# untitled.net
KiCad netlist of a schematic drawn in EAGLE
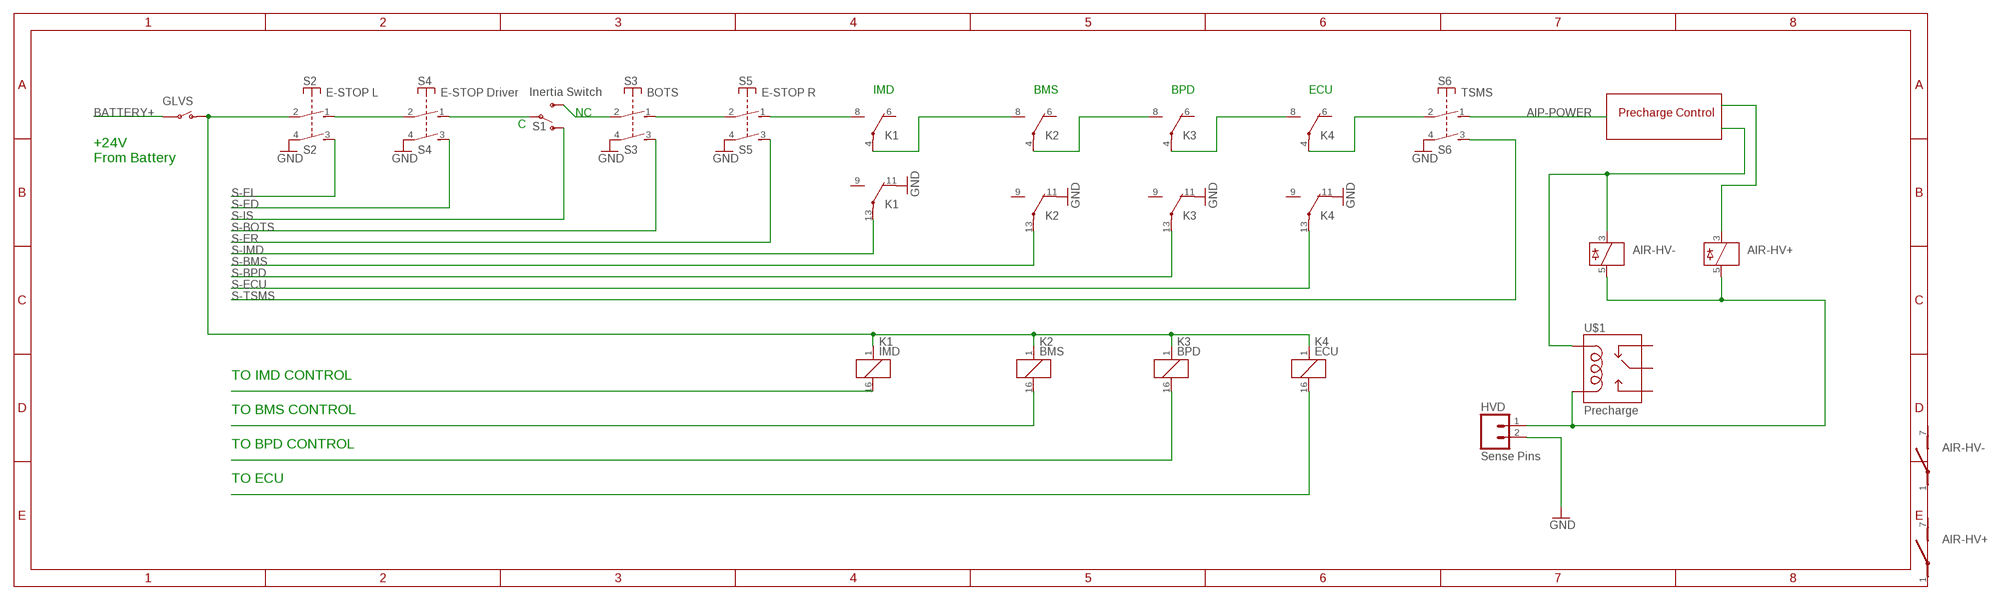
[diagram p0: schematic, sheet 1]
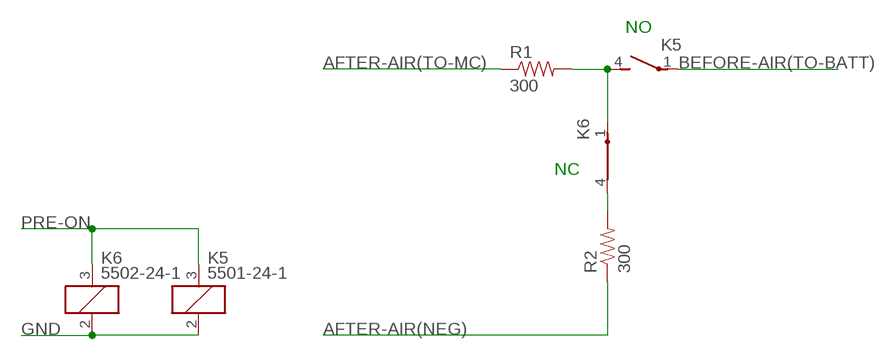
[diagram p1: schematic, sheet 2]

(export (version "E")
  (design (tool "Eeschema 10.0.6"))
  (components
    (comp (ref "K5")
      (value "5501-24-1")
      (footprint "eagle-import:5500")
      (libsource (lib "eagle-import") (part "5501-24-1"))
    )
    (comp (ref "K6")
      (value "5502-24-1")
      (footprint "eagle-import:5500")
      (libsource (lib "eagle-import") (part "5502-24-1"))
    )
    (comp (ref "R1")
      (value "300")
      (footprint "eagle-import:0603-RES")
      (libsource (lib "eagle-import") (part "1MOHM1/10W1%(0603)"))
    )
    (comp (ref "R2")
      (value "300")
      (footprint "eagle-import:0603-RES")
      (libsource (lib "eagle-import") (part "1MOHM1/10W1%(0603)"))
    )
    (comp (ref "AIR-HV+")
      (value "35701331")
      (footprint "eagle-import:REED")
      (libsource (lib "eagle-import") (part "35701331"))
    )
    (comp (ref "AIR-HV-")
      (value "35701331")
      (footprint "eagle-import:REED")
      (libsource (lib "eagle-import") (part "35701331"))
    )
    (comp (ref "GLVS")
      (value "SWITCH-SPST-2TV")
      (footprint "eagle-import:SWITCH-SPST-VERTICAL")
      (libsource (lib "eagle-import") (part "SWITCH-SPST-2TV"))
    )
    (comp (ref "HVD")
      (value "Sense Pins")
      (footprint "eagle-import:JST-2-SMD")
      (libsource (lib "eagle-import") (part "M02-JST-2MM-SMT"))
    )
    (comp (ref "K1")
      (value "IMD")
      (footprint "eagle-import:BT-XX-S")
      (libsource (lib "eagle-import") (part "BT--S6"))
    )
    (comp (ref "K2")
      (value "BMS")
      (footprint "eagle-import:BT-XX-S")
      (libsource (lib "eagle-import") (part "BT--S6"))
    )
    (comp (ref "K3")
      (value "BPD")
      (footprint "eagle-import:BT-XX-S")
      (libsource (lib "eagle-import") (part "BT--S6"))
    )
    (comp (ref "K4")
      (value "ECU")
      (footprint "eagle-import:BT-XX-S")
      (libsource (lib "eagle-import") (part "BT--S6"))
    )
    (comp (ref "S1")
      (value "Inertia Switch")
      (footprint "eagle-import:SWITCHE-DPDT")
      (libsource (lib "eagle-import") (part "SWITCH-SPDTPTH2"))
    )
    (comp (ref "S2")
      (value "E-STOP L")
      (footprint "eagle-import:PVA1F")
      (libsource (lib "eagle-import") (part "PVA1"))
    )
    (comp (ref "S3")
      (value "BOTS")
      (footprint "eagle-import:PVA1F")
      (libsource (lib "eagle-import") (part "PVA1"))
    )
    (comp (ref "S4")
      (value "E-STOP Driver")
      (footprint "eagle-import:PVA1F")
      (libsource (lib "eagle-import") (part "PVA1"))
    )
    (comp (ref "S5")
      (value "E-STOP R")
      (footprint "eagle-import:PVA1F")
      (libsource (lib "eagle-import") (part "PVA1"))
    )
    (comp (ref "S6")
      (value "TSMS")
      (footprint "eagle-import:PVA1F")
      (libsource (lib "eagle-import") (part "PVA1"))
    )
    (comp (ref "U$1")
      (value "Precharge")
      (footprint "eagle-import:RELAY-G5Q")
      (libsource (lib "eagle-import") (part "RELAYPTH"))
    )
  )
  (nets
    (net (code "1") (name "AFTER-AIR(NEG)") (class "Default")
      (node (ref "R2") (pin "1") (pinfunction "1_1") (pintype "passive"))
    )
    (net (code "2") (name "AFTER-AIR(TO-MC)") (class "Default")
      (node (ref "R1") (pin "1") (pinfunction "1_1") (pintype "passive"))
    )
    (net (code "3") (name "AIP-POWER") (class "Default")
      (node (ref "S6") (pin "1") (pinfunction "S_1") (pintype "passive"))
    )
    (net (code "4") (name "BATTERY+") (class "Default")
      (node (ref "GLVS") (pin "2") (pinfunction "P_2") (pintype "passive"))
    )
    (net (code "5") (name "BEFORE-AIR(TO-BATT)") (class "Default")
      (node (ref "K5") (pin "1") (pinfunction "P_1") (pintype "passive"))
    )
    (net (code "6") (name "GND") (class "Default")
      (node (ref "HVD") (pin "2") (pinfunction "1_2") (pintype "passive"))
      (node (ref "K1") (pin "11") (pinfunction "O_11") (pintype "passive"))
      (node (ref "K2") (pin "11") (pinfunction "O_11") (pintype "passive"))
      (node (ref "K3") (pin "11") (pinfunction "O_11") (pintype "passive"))
      (node (ref "K4") (pin "11") (pinfunction "O_11") (pintype "passive"))
      (node (ref "K5") (pin "2") (pinfunction "-_2") (pintype "passive"))
      (node (ref "K6") (pin "2") (pinfunction "-_2") (pintype "passive"))
      (node (ref "S2") (pin "4") (pinfunction "P_4") (pintype "passive"))
      (node (ref "S3") (pin "4") (pinfunction "P_4") (pintype "passive"))
      (node (ref "S4") (pin "4") (pinfunction "P_4") (pintype "passive"))
      (node (ref "S5") (pin "4") (pinfunction "P_4") (pintype "passive"))
      (node (ref "S6") (pin "4") (pinfunction "P_4") (pintype "passive"))
    )
    (net (code "7") (name "Net-(GLVS-O)") (class "Default")
      (node (ref "GLVS") (pin "1") (pinfunction "O_1") (pintype "passive"))
      (node (ref "K1") (pin "1") (pinfunction "1_1") (pintype "passive"))
      (node (ref "K2") (pin "1") (pinfunction "1_1") (pintype "passive"))
      (node (ref "K3") (pin "1") (pinfunction "1_1") (pintype "passive"))
      (node (ref "K4") (pin "1") (pinfunction "1_1") (pintype "passive"))
      (node (ref "S2") (pin "2") (pinfunction "P_2") (pintype "passive"))
    )
    (net (code "8") (name "Net-(HVD-2)") (class "Default")
      (node (ref "AIR-HV+") (pin "5") (pinfunction "5_5") (pintype "passive"))
      (node (ref "AIR-HV-") (pin "5") (pinfunction "5_5") (pintype "passive"))
      (node (ref "HVD") (pin "1") (pinfunction "2_1") (pintype "passive"))
      (node (ref "U$1") (pin "1") (pinfunction "COIL2_1") (pintype "bidirectional"))
    )
    (net (code "9") (name "Net-(K1A-P)") (class "Default")
      (node (ref "K1") (pin "4") (pinfunction "P_4") (pintype "passive"))
      (node (ref "K2") (pin "8") (pinfunction "S_8") (pintype "passive"))
    )
    (net (code "10") (name "Net-(K1A-S)") (class "Default")
      (node (ref "K1") (pin "8") (pinfunction "S_8") (pintype "passive"))
      (node (ref "S5") (pin "1") (pinfunction "S_1") (pintype "passive"))
    )
    (net (code "11") (name "Net-(K2A-P)") (class "Default")
      (node (ref "K2") (pin "4") (pinfunction "P_4") (pintype "passive"))
      (node (ref "K3") (pin "8") (pinfunction "S_8") (pintype "passive"))
    )
    (net (code "12") (name "Net-(K3A-P)") (class "Default")
      (node (ref "K3") (pin "4") (pinfunction "P_4") (pintype "passive"))
      (node (ref "K4") (pin "8") (pinfunction "S_8") (pintype "passive"))
    )
    (net (code "13") (name "Net-(K4A-P)") (class "Default")
      (node (ref "K4") (pin "4") (pinfunction "P_4") (pintype "passive"))
      (node (ref "S6") (pin "2") (pinfunction "P_2") (pintype "passive"))
    )
    (net (code "14") (name "Net-(K5B-S)") (class "Default")
      (node (ref "K5") (pin "4") (pinfunction "S_4") (pintype "passive"))
      (node (ref "K6") (pin "1") (pinfunction "P_1") (pintype "passive"))
      (node (ref "R1") (pin "2") (pinfunction "2_2") (pintype "passive"))
    )
    (net (code "15") (name "Net-(K6B-S)") (class "Default")
      (node (ref "K6") (pin "4") (pinfunction "S_4") (pintype "passive"))
      (node (ref "R2") (pin "2") (pinfunction "2_2") (pintype "passive"))
    )
    (net (code "16") (name "Net-(S1-P)") (class "Default")
      (node (ref "S1") (pin "2") (pinfunction "P_2") (pintype "passive"))
      (node (ref "S4") (pin "1") (pinfunction "S_1") (pintype "passive"))
    )
    (net (code "17") (name "Net-(S1-S)") (class "Default")
      (node (ref "S1") (pin "3") (pinfunction "S_3") (pintype "passive"))
      (node (ref "S3") (pin "2") (pinfunction "P_2") (pintype "passive"))
    )
    (net (code "18") (name "Net-(S2A-S)") (class "Default")
      (node (ref "S2") (pin "1") (pinfunction "S_1") (pintype "passive"))
      (node (ref "S4") (pin "2") (pinfunction "P_2") (pintype "passive"))
    )
    (net (code "19") (name "Net-(S3A-S)") (class "Default")
      (node (ref "S3") (pin "1") (pinfunction "S_1") (pintype "passive"))
      (node (ref "S5") (pin "2") (pinfunction "P_2") (pintype "passive"))
    )
    (net (code "20") (name "Net-(U$1-COIL1)") (class "Default")
      (node (ref "AIR-HV-") (pin "3") (pinfunction "3_3") (pintype "passive"))
      (node (ref "U$1") (pin "5") (pinfunction "COIL1_5") (pintype "bidirectional"))
    )
    (net (code "21") (name "PRE-ON") (class "Default")
      (node (ref "K5") (pin "3") (pinfunction "+_3") (pintype "passive"))
      (node (ref "K6") (pin "3") (pinfunction "+_3") (pintype "passive"))
    )
    (net (code "22") (name "S-BMS") (class "Default")
      (node (ref "K2") (pin "13") (pinfunction "P_13") (pintype "passive"))
    )
    (net (code "23") (name "S-BOTS") (class "Default")
      (node (ref "S3") (pin "3") (pinfunction "S_3") (pintype "passive"))
    )
    (net (code "24") (name "S-BPD") (class "Default")
      (node (ref "K3") (pin "13") (pinfunction "P_13") (pintype "passive"))
    )
    (net (code "25") (name "S-ECU") (class "Default")
      (node (ref "K4") (pin "13") (pinfunction "P_13") (pintype "passive"))
    )
    (net (code "26") (name "S-ED") (class "Default")
      (node (ref "S4") (pin "3") (pinfunction "S_3") (pintype "passive"))
    )
    (net (code "27") (name "S-EL") (class "Default")
      (node (ref "S2") (pin "3") (pinfunction "S_3") (pintype "passive"))
    )
    (net (code "28") (name "S-ER") (class "Default")
      (node (ref "S5") (pin "3") (pinfunction "S_3") (pintype "passive"))
    )
    (net (code "29") (name "S-IMD") (class "Default")
      (node (ref "K1") (pin "13") (pinfunction "P_13") (pintype "passive"))
    )
    (net (code "30") (name "S-IS") (class "Default")
      (node (ref "S1") (pin "1") (pinfunction "O_1") (pintype "passive"))
    )
    (net (code "31") (name "S-TSMS") (class "Default")
      (node (ref "S6") (pin "3") (pinfunction "S_3") (pintype "passive"))
    )
    (net (code "32") (name "unconnected-(AIR-HV+-Pad3)") (class "Default")
      (node (ref "AIR-HV+") (pin "3") (pinfunction "3_3") (pintype "passive"))
    )
    (net (code "33") (name "unconnected-(AIR-HV+B-P-Pad1)") (class "Default")
      (node (ref "AIR-HV+") (pin "1") (pinfunction "P_1") (pintype "passive"))
    )
    (net (code "34") (name "unconnected-(AIR-HV+B-S-Pad7)") (class "Default")
      (node (ref "AIR-HV+") (pin "7") (pinfunction "S_7") (pintype "passive"))
    )
    (net (code "35") (name "unconnected-(AIR-HV-B-P-Pad1)") (class "Default")
      (node (ref "AIR-HV-") (pin "1") (pinfunction "P_1") (pintype "passive"))
    )
    (net (code "36") (name "unconnected-(AIR-HV-B-S-Pad7)") (class "Default")
      (node (ref "AIR-HV-") (pin "7") (pinfunction "S_7") (pintype "passive"))
    )
    (net (code "37") (name "unconnected-(K1A-O-Pad6)") (class "Default")
      (node (ref "K1") (pin "6") (pinfunction "O_6") (pintype "passive"))
    )
    (net (code "38") (name "unconnected-(K1B-S-Pad9)") (class "Default")
      (node (ref "K1") (pin "9") (pinfunction "S_9") (pintype "passive"))
    )
    (net (code "39") (name "unconnected-(K1C-2-Pad16)") (class "Default")
      (node (ref "K1") (pin "16") (pinfunction "2_16") (pintype "passive"))
    )
    (net (code "40") (name "unconnected-(K2A-O-Pad6)") (class "Default")
      (node (ref "K2") (pin "6") (pinfunction "O_6") (pintype "passive"))
    )
    (net (code "41") (name "unconnected-(K2B-S-Pad9)") (class "Default")
      (node (ref "K2") (pin "9") (pinfunction "S_9") (pintype "passive"))
    )
    (net (code "42") (name "unconnected-(K2C-2-Pad16)") (class "Default")
      (node (ref "K2") (pin "16") (pinfunction "2_16") (pintype "passive"))
    )
    (net (code "43") (name "unconnected-(K3A-O-Pad6)") (class "Default")
      (node (ref "K3") (pin "6") (pinfunction "O_6") (pintype "passive"))
    )
    (net (code "44") (name "unconnected-(K3B-S-Pad9)") (class "Default")
      (node (ref "K3") (pin "9") (pinfunction "S_9") (pintype "passive"))
    )
    (net (code "45") (name "unconnected-(K3C-2-Pad16)") (class "Default")
      (node (ref "K3") (pin "16") (pinfunction "2_16") (pintype "passive"))
    )
    (net (code "46") (name "unconnected-(K4A-O-Pad6)") (class "Default")
      (node (ref "K4") (pin "6") (pinfunction "O_6") (pintype "passive"))
    )
    (net (code "47") (name "unconnected-(K4B-S-Pad9)") (class "Default")
      (node (ref "K4") (pin "9") (pinfunction "S_9") (pintype "passive"))
    )
    (net (code "48") (name "unconnected-(K4C-2-Pad16)") (class "Default")
      (node (ref "K4") (pin "16") (pinfunction "2_16") (pintype "passive"))
    )
    (net (code "49") (name "unconnected-(U$1-MAIN-Pad2)") (class "Default")
      (node (ref "U$1") (pin "2") (pinfunction "MAIN_2") (pintype "bidirectional"))
    )
    (net (code "50") (name "unconnected-(U$1-NC-Pad4)") (class "Default")
      (node (ref "U$1") (pin "4") (pinfunction "NC_4") (pintype "bidirectional"))
    )
    (net (code "51") (name "unconnected-(U$1-NO-Pad3)") (class "Default")
      (node (ref "U$1") (pin "3") (pinfunction "NO_3") (pintype "bidirectional"))
    )
  )
)
